# battery_board.net
KiCad netlist of a schematic drawn in EAGLE
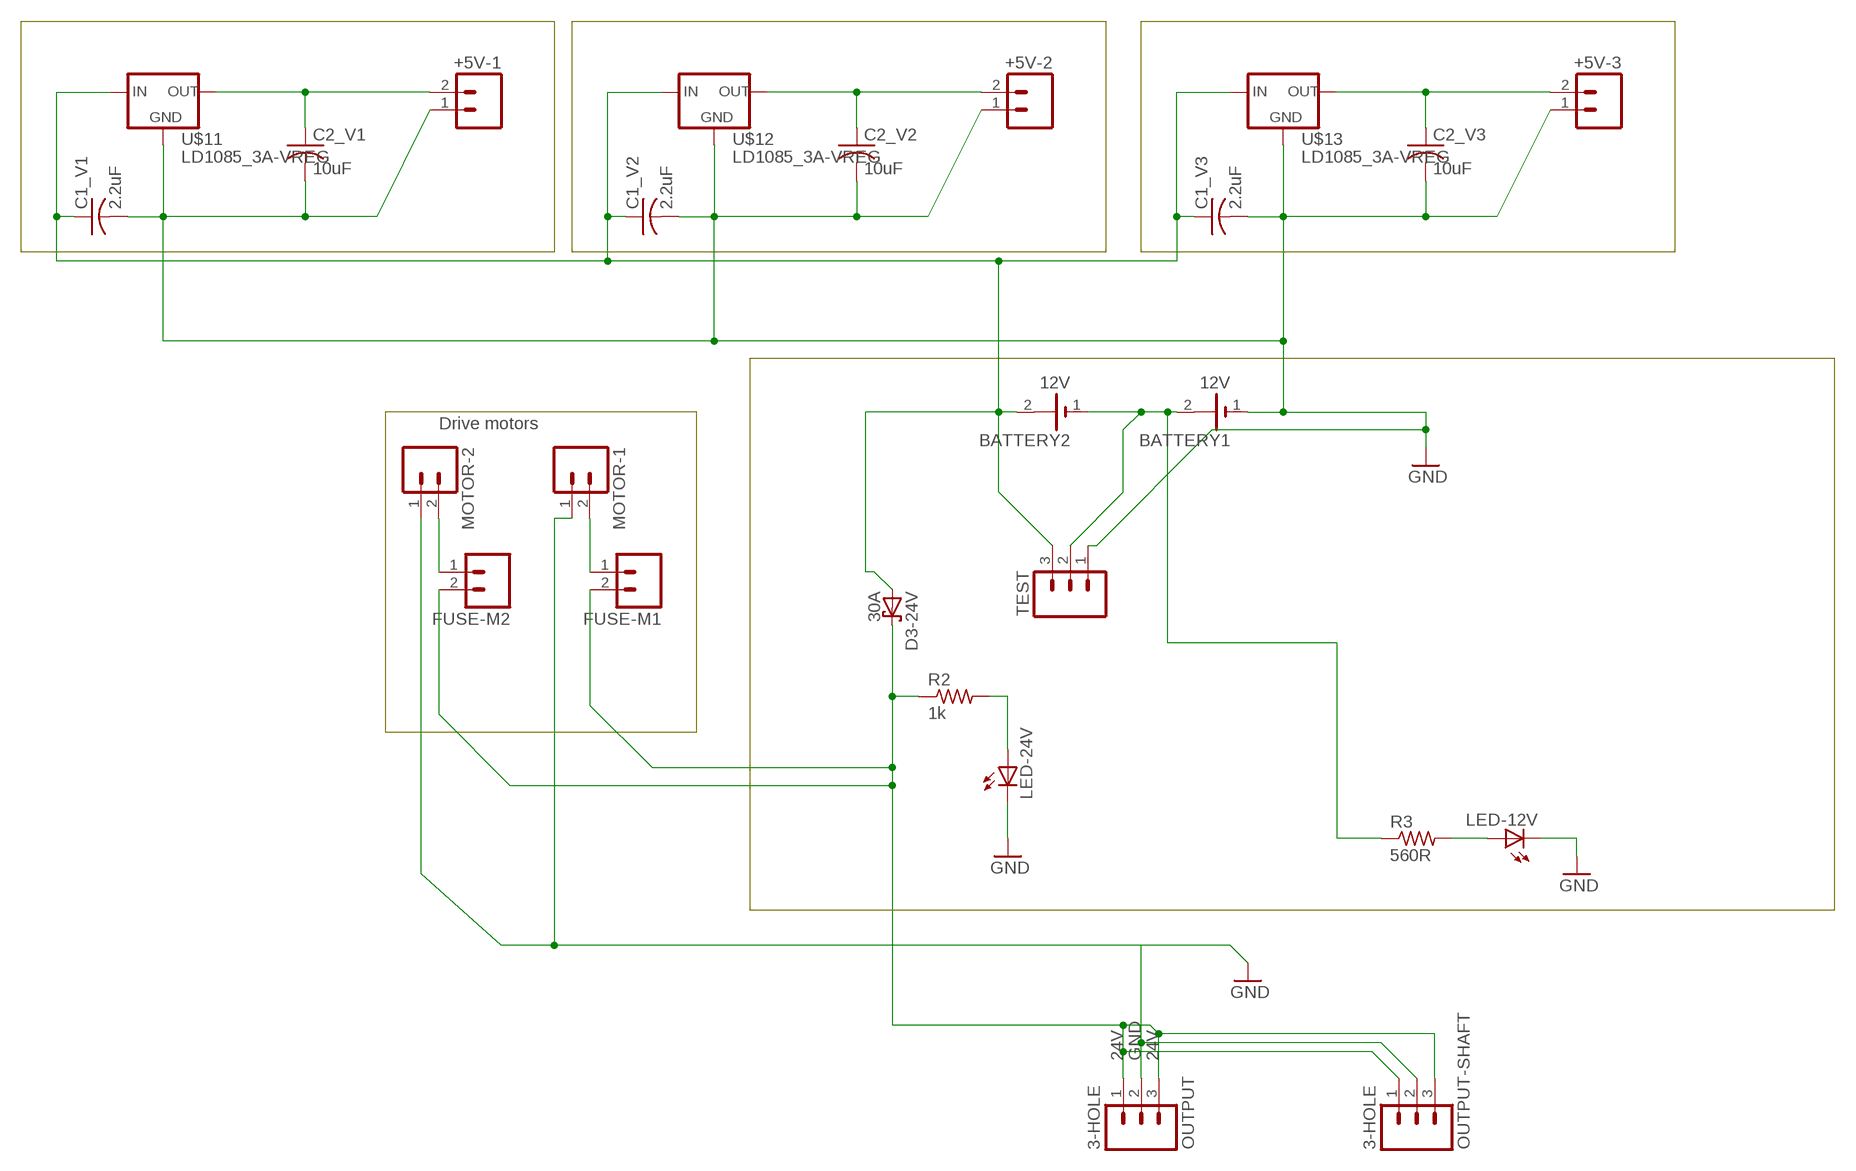
[diagram p0: schematic, sheet 1]

(export (version "E")
  (design (tool "Eeschema 10.0.6"))
  (components
    (comp (ref "+5V-1")
      (value "2-HOLESSC3.81MM")
      (footprint "eagle-import:SCREWTERMINAL-3.81MM")
      (libsource (lib "eagle-import") (part "2-HOLESSC3.81MM"))
    )
    (comp (ref "+5V-2")
      (value "2-HOLESSC3.81MM")
      (footprint "eagle-import:SCREWTERMINAL-3.81MM")
      (libsource (lib "eagle-import") (part "2-HOLESSC3.81MM"))
    )
    (comp (ref "+5V-3")
      (value "2-HOLESSC3.81MM")
      (footprint "eagle-import:SCREWTERMINAL-3.81MM")
      (libsource (lib "eagle-import") (part "2-HOLESSC3.81MM"))
    )
    (comp (ref "BATTERY1")
      (value "12V")
      (footprint "eagle-import:SCREWTERMINAL-5MM-2")
      (libsource (lib "eagle-import") (part "BATTERY-ST"))
    )
    (comp (ref "BATTERY2")
      (value "12V")
      (footprint "eagle-import:SCREWTERMINAL-5MM-2")
      (libsource (lib "eagle-import") (part "BATTERY-ST"))
    )
    (comp (ref "C1_V1")
      (value "2.2uF")
      (footprint "eagle-import:C050-024X044")
      (libsource (lib "eagle-import") (part "CAPACITOR"))
    )
    (comp (ref "C1_V2")
      (value "2.2uF")
      (footprint "eagle-import:C050-024X044")
      (libsource (lib "eagle-import") (part "CAPACITOR"))
    )
    (comp (ref "C1_V3")
      (value "2.2uF")
      (footprint "eagle-import:C050-024X044")
      (libsource (lib "eagle-import") (part "CAPACITOR"))
    )
    (comp (ref "C2_V1")
      (value "10uF")
      (footprint "eagle-import:C050-024X044")
      (libsource (lib "eagle-import") (part "CAPACITOR"))
    )
    (comp (ref "C2_V2")
      (value "10uF")
      (footprint "eagle-import:C050-024X044")
      (libsource (lib "eagle-import") (part "CAPACITOR"))
    )
    (comp (ref "C2_V3")
      (value "10uF")
      (footprint "eagle-import:C050-024X044")
      (libsource (lib "eagle-import") (part "CAPACITOR"))
    )
    (comp (ref "D3-24V")
      (value "30A")
      (footprint "eagle-import:TO22-DIODE-H")
      (libsource (lib "eagle-import") (part "POWER_RECTIFIER-H"))
    )
    (comp (ref "FUSE-M1")
      (value "3A")
      (footprint "eagle-import:SCREWTERMINAL-5MM-2")
      (libsource (lib "eagle-import") (part "2-HOLESSC5MM"))
    )
    (comp (ref "FUSE-M2")
      (value "3A")
      (footprint "eagle-import:SCREWTERMINAL-5MM-2")
      (libsource (lib "eagle-import") (part "2-HOLESSC5MM"))
    )
    (comp (ref "LED-12V")
      (value "LED-5MM")
      (footprint "eagle-import:LED5MM")
      (libsource (lib "eagle-import") (part "LED-5MM"))
    )
    (comp (ref "LED-24V")
      (value "LED-5MM")
      (footprint "eagle-import:LED5MM")
      (libsource (lib "eagle-import") (part "LED-5MM"))
    )
    (comp (ref "MOTOR-1")
      (value "2-HOLESSC5MM")
      (footprint "eagle-import:SCREWTERMINAL-5MM-2")
      (libsource (lib "eagle-import") (part "2-HOLESSC5MM"))
    )
    (comp (ref "MOTOR-2")
      (value "2-HOLESSC5MM")
      (footprint "eagle-import:SCREWTERMINAL-5MM-2")
      (libsource (lib "eagle-import") (part "2-HOLESSC5MM"))
    )
    (comp (ref "OUTPUT")
      (value "3-HOLE")
      (footprint "eagle-import:SCREWTERMINAL-5MM-3@1")
      (libsource (lib "eagle-import") (part "3-HOLE"))
    )
    (comp (ref "OUTPUT-SHAFT")
      (value "3-HOLE")
      (footprint "eagle-import:SCREWTERMINAL-5MM-3@1")
      (libsource (lib "eagle-import") (part "3-HOLE"))
    )
    (comp (ref "R2")
      (value "1k")
      (footprint "eagle-import:0309_15")
      (libsource (lib "eagle-import") (part "RESISTOR0309/15"))
    )
    (comp (ref "R3")
      (value "560R")
      (footprint "eagle-import:0309_15")
      (libsource (lib "eagle-import") (part "RESISTOR0309/15"))
    )
    (comp (ref "TEST")
      (value "M03PTH")
      (footprint "eagle-import:1X03")
      (libsource (lib "eagle-import") (part "M03PTH"))
    )
    (comp (ref "U$11")
      (value "LD1085_3A-VREG")
      (footprint "eagle-import:TO220V-HEATSINK2")
      (libsource (lib "eagle-import") (part "LD1085_3A-VREG"))
    )
    (comp (ref "U$12")
      (value "LD1085_3A-VREG")
      (footprint "eagle-import:TO220V-HEATSINK2")
      (libsource (lib "eagle-import") (part "LD1085_3A-VREG"))
    )
    (comp (ref "U$13")
      (value "LD1085_3A-VREG")
      (footprint "eagle-import:TO220V-HEATSINK2")
      (libsource (lib "eagle-import") (part "LD1085_3A-VREG"))
    )
  )
  (nets
    (net (code "1") (name "/24V") (class "Default")
      (node (ref "D3-24V") (pin "P$2") (pinfunction "C_P$2") (pintype "passive"))
      (node (ref "FUSE-M1") (pin "2") (pinfunction "2_2") (pintype "passive"))
      (node (ref "FUSE-M2") (pin "2") (pinfunction "2_2") (pintype "passive"))
      (node (ref "OUTPUT") (pin "1") (pinfunction "1_1") (pintype "passive"))
      (node (ref "OUTPUT") (pin "3") (pinfunction "3_3") (pintype "passive"))
      (node (ref "OUTPUT-SHAFT") (pin "1") (pinfunction "1_1") (pintype "passive"))
      (node (ref "OUTPUT-SHAFT") (pin "3") (pinfunction "3_3") (pintype "passive"))
      (node (ref "R2") (pin "1") (pinfunction "1_1") (pintype "passive"))
    )
    (net (code "2") (name "GND") (class "Default")
      (node (ref "+5V-1") (pin "1") (pinfunction "1_1") (pintype "passive"))
      (node (ref "+5V-2") (pin "1") (pinfunction "1_1") (pintype "passive"))
      (node (ref "+5V-3") (pin "1") (pinfunction "1_1") (pintype "passive"))
      (node (ref "BATTERY1") (pin "1") (pinfunction "-_1") (pintype "passive"))
      (node (ref "C1_V1") (pin "2") (pinfunction "2_2") (pintype "passive"))
      (node (ref "C1_V2") (pin "2") (pinfunction "2_2") (pintype "passive"))
      (node (ref "C1_V3") (pin "2") (pinfunction "2_2") (pintype "passive"))
      (node (ref "C2_V1") (pin "2") (pinfunction "2_2") (pintype "passive"))
      (node (ref "C2_V2") (pin "2") (pinfunction "2_2") (pintype "passive"))
      (node (ref "C2_V3") (pin "2") (pinfunction "2_2") (pintype "passive"))
      (node (ref "LED-12V") (pin "K") (pinfunction "C_K") (pintype "passive"))
      (node (ref "LED-24V") (pin "K") (pinfunction "C_K") (pintype "passive"))
      (node (ref "MOTOR-1") (pin "1") (pinfunction "1_1") (pintype "passive"))
      (node (ref "MOTOR-2") (pin "1") (pinfunction "1_1") (pintype "passive"))
      (node (ref "OUTPUT") (pin "2") (pinfunction "2_2") (pintype "passive"))
      (node (ref "OUTPUT-SHAFT") (pin "2") (pinfunction "2_2") (pintype "passive"))
      (node (ref "TEST") (pin "1") (pinfunction "1_1") (pintype "passive"))
      (node (ref "U$11") (pin "1") (pinfunction "GND_1") (pintype "input"))
      (node (ref "U$12") (pin "1") (pinfunction "GND_1") (pintype "input"))
      (node (ref "U$13") (pin "1") (pinfunction "GND_1") (pintype "input"))
    )
    (net (code "3") (name "Net-(BATTERY1-+)") (class "Default")
      (node (ref "BATTERY1") (pin "2") (pinfunction "+_2") (pintype "passive"))
      (node (ref "BATTERY2") (pin "1") (pinfunction "-_1") (pintype "passive"))
      (node (ref "R3") (pin "1") (pinfunction "1_1") (pintype "passive"))
      (node (ref "TEST") (pin "2") (pinfunction "2_2") (pintype "passive"))
    )
    (net (code "4") (name "Net-(BATTERY2-+)") (class "Default")
      (node (ref "BATTERY2") (pin "2") (pinfunction "+_2") (pintype "passive"))
      (node (ref "C1_V1") (pin "1") (pinfunction "1_1") (pintype "passive"))
      (node (ref "C1_V2") (pin "1") (pinfunction "1_1") (pintype "passive"))
      (node (ref "C1_V3") (pin "1") (pinfunction "1_1") (pintype "passive"))
      (node (ref "D3-24V") (pin "P$1") (pinfunction "A_P$1") (pintype "passive"))
      (node (ref "TEST") (pin "3") (pinfunction "3_3") (pintype "passive"))
      (node (ref "U$11") (pin "3") (pinfunction "IN_3") (pintype "input"))
      (node (ref "U$12") (pin "3") (pinfunction "IN_3") (pintype "input"))
      (node (ref "U$13") (pin "3") (pinfunction "IN_3") (pintype "input"))
    )
    (net (code "5") (name "Net-(FUSE-M1-Pad1)") (class "Default")
      (node (ref "FUSE-M1") (pin "1") (pinfunction "1_1") (pintype "passive"))
      (node (ref "MOTOR-1") (pin "2") (pinfunction "2_2") (pintype "passive"))
    )
    (net (code "6") (name "Net-(FUSE-M2-Pad1)") (class "Default")
      (node (ref "FUSE-M2") (pin "1") (pinfunction "1_1") (pintype "passive"))
      (node (ref "MOTOR-2") (pin "2") (pinfunction "2_2") (pintype "passive"))
    )
    (net (code "7") (name "Net-(LED-12V-PadA)") (class "Default")
      (node (ref "LED-12V") (pin "A") (pinfunction "A_A") (pintype "passive"))
      (node (ref "R3") (pin "2") (pinfunction "2_2") (pintype "passive"))
    )
    (net (code "8") (name "Net-(LED-24V-PadA)") (class "Default")
      (node (ref "LED-24V") (pin "A") (pinfunction "A_A") (pintype "passive"))
      (node (ref "R2") (pin "2") (pinfunction "2_2") (pintype "passive"))
    )
    (net (code "9") (name "Net-(U$11-OUT)") (class "Default")
      (node (ref "+5V-1") (pin "2") (pinfunction "2_2") (pintype "passive"))
      (node (ref "C2_V1") (pin "1") (pinfunction "1_1") (pintype "passive"))
      (node (ref "U$11") (pin "2") (pinfunction "OUT_2") (pintype "passive"))
    )
    (net (code "10") (name "Net-(U$12-OUT)") (class "Default")
      (node (ref "+5V-2") (pin "2") (pinfunction "2_2") (pintype "passive"))
      (node (ref "C2_V2") (pin "1") (pinfunction "1_1") (pintype "passive"))
      (node (ref "U$12") (pin "2") (pinfunction "OUT_2") (pintype "passive"))
    )
    (net (code "11") (name "Net-(U$13-OUT)") (class "Default")
      (node (ref "+5V-3") (pin "2") (pinfunction "2_2") (pintype "passive"))
      (node (ref "C2_V3") (pin "1") (pinfunction "1_1") (pintype "passive"))
      (node (ref "U$13") (pin "2") (pinfunction "OUT_2") (pintype "passive"))
    )
  )
)
